# fpga-bank1-outside.net
KiCad netlist of a schematic drawn in Altium Designer
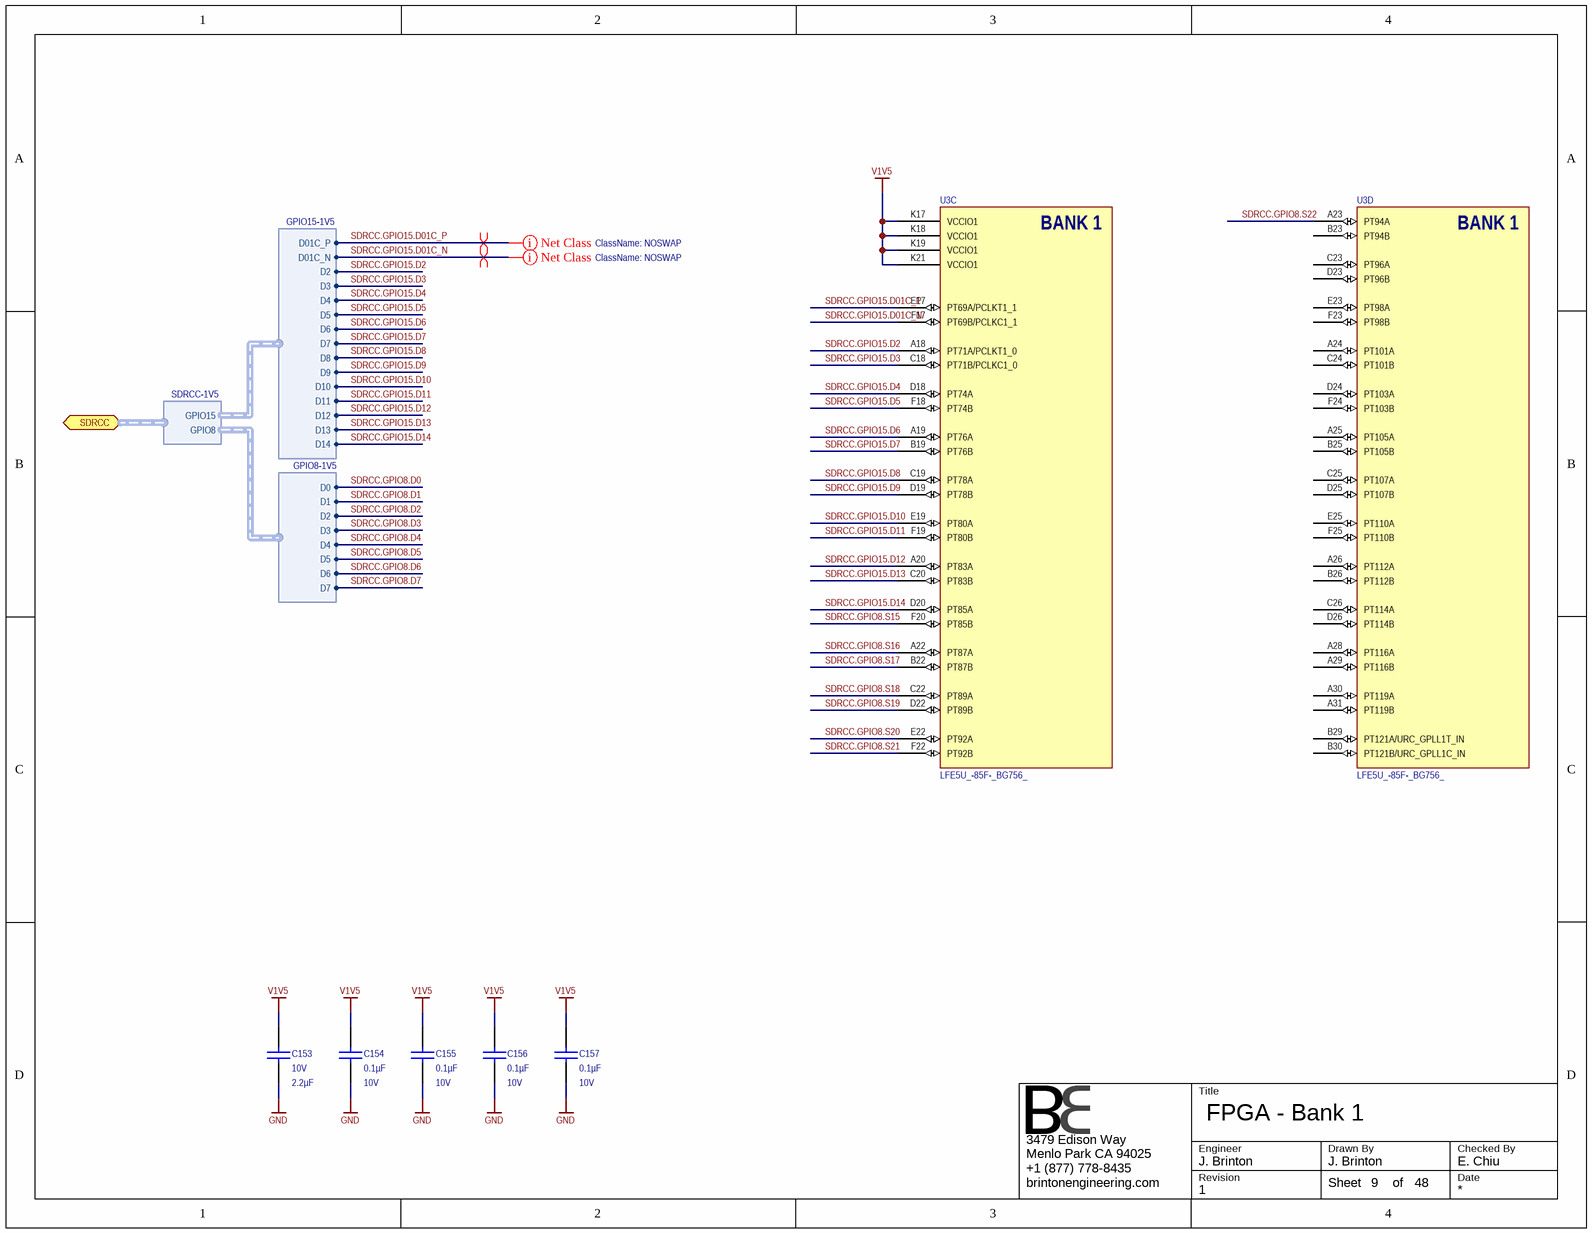
[diagram p0: fpga-bank1-outside.SchDoc]

(export (version "E")
  (design (tool "Eeschema 10.0.6"))
  (components
    (comp (ref "C153")
      (value "GRM188R71A225KE15D")
      (footprint "CAPC1608X90N")
      (description "CAP CER 2.2UF 10V 10% X7R 0603")
      (fields
        (field (name "MANUFACTURER") "Murata Electronics North America")
        (field (name "TOLERANCE") "±10%")
        (field (name "VOLTAGE - RATED") "10V")
        (field (name "CAPACITANCE") "2.2µF")
      )
      (libsource (lib "murata") (part "GRM188R71A225KE15D"))
    )
    (comp (ref "C154")
      (value "GRM155R71A104KA01J")
      (footprint "CAPC1005X56N")
      (description "CAP CER 0.1UF 10V 10% X7R 0402")
      (fields
        (field (name "MANUFACTURER") "Murata Electronics North America")
        (field (name "TOLERANCE") "±10%")
        (field (name "CAPACITANCE") "0.1µF")
        (field (name "VOLTAGE - RATED") "10V")
      )
      (libsource (lib "murata") (part "GRM155R71A104KA01J"))
    )
    (comp (ref "C155")
      (value "GRM155R71A104KA01J")
      (footprint "CAPC1005X56N")
      (description "CAP CER 0.1UF 10V 10% X7R 0402")
      (fields
        (field (name "MANUFACTURER") "Murata Electronics North America")
        (field (name "TOLERANCE") "±10%")
        (field (name "CAPACITANCE") "0.1µF")
        (field (name "VOLTAGE - RATED") "10V")
      )
      (libsource (lib "murata") (part "GRM155R71A104KA01J"))
    )
    (comp (ref "C156")
      (value "GRM155R71A104KA01J")
      (footprint "CAPC1005X56N")
      (description "CAP CER 0.1UF 10V 10% X7R 0402")
      (fields
        (field (name "MANUFACTURER") "Murata Electronics North America")
        (field (name "TOLERANCE") "±10%")
        (field (name "CAPACITANCE") "0.1µF")
        (field (name "VOLTAGE - RATED") "10V")
      )
      (libsource (lib "murata") (part "GRM155R71A104KA01J"))
    )
    (comp (ref "C157")
      (value "GRM155R71A104KA01J")
      (footprint "CAPC1005X56N")
      (description "CAP CER 0.1UF 10V 10% X7R 0402")
      (fields
        (field (name "MANUFACTURER") "Murata Electronics North America")
        (field (name "TOLERANCE") "±10%")
        (field (name "CAPACITANCE") "0.1µF")
        (field (name "VOLTAGE - RATED") "10V")
      )
      (libsource (lib "murata") (part "GRM155R71A104KA01J"))
    )
    (comp (ref "U3")
      (value "LFE5U_-85F-_BG756_")
      (footprint "lattice:caBGA756")
      (description "ECP5 FPGA, 85k LUT, 756-caBGA")
      (fields (field (name "MANUFACTURER") "Lattice Semiconductor"))
      (libsource (lib "lattice") (part "LFE5U_-85F-_BG756_"))
    )
  )
  (nets
    (net (code "11") (name "/SDRCC.GPIO8.S15") (class "Default")
      (node (ref "U3") (pin "F20") (pinfunction "PT85B_F20") (pintype "bidirectional"))
    )
    (net (code "12") (name "/SDRCC.GPIO8.S16") (class "Default")
      (node (ref "U3") (pin "A22") (pinfunction "PT87A_A22") (pintype "bidirectional"))
    )
    (net (code "13") (name "/SDRCC.GPIO8.S17") (class "Default")
      (node (ref "U3") (pin "B22") (pinfunction "PT87B_B22") (pintype "bidirectional"))
    )
    (net (code "14") (name "/SDRCC.GPIO8.S18") (class "Default")
      (node (ref "U3") (pin "C22") (pinfunction "PT89A_C22") (pintype "bidirectional"))
    )
    (net (code "15") (name "/SDRCC.GPIO8.S19") (class "Default")
      (node (ref "U3") (pin "D22") (pinfunction "PT89B_D22") (pintype "bidirectional"))
    )
    (net (code "16") (name "/SDRCC.GPIO8.S20") (class "Default")
      (node (ref "U3") (pin "E22") (pinfunction "PT92A_E22") (pintype "bidirectional"))
    )
    (net (code "17") (name "/SDRCC.GPIO8.S21") (class "Default")
      (node (ref "U3") (pin "F22") (pinfunction "PT92B_F22") (pintype "bidirectional"))
    )
    (net (code "18") (name "/SDRCC.GPIO8.S22") (class "Default")
      (node (ref "U3") (pin "A23") (pinfunction "PT94A_A23") (pintype "bidirectional"))
    )
    (net (code "19") (name "/SDRCC.GPIO15.D01C_N") (class "Default")
      (node (ref "U3") (pin "F17") (pinfunction "PT69B/PCLKC1_1_F17") (pintype "bidirectional"))
    )
    (net (code "20") (name "/SDRCC.GPIO15.D01C_P") (class "Default")
      (node (ref "U3") (pin "E17") (pinfunction "PT69A/PCLKT1_1_E17") (pintype "bidirectional"))
    )
    (net (code "21") (name "/SDRCC.GPIO15.D2") (class "Default")
      (node (ref "U3") (pin "A18") (pinfunction "PT71A/PCLKT1_0_A18") (pintype "bidirectional"))
    )
    (net (code "22") (name "/SDRCC.GPIO15.D3") (class "Default")
      (node (ref "U3") (pin "C18") (pinfunction "PT71B/PCLKC1_0_C18") (pintype "bidirectional"))
    )
    (net (code "23") (name "/SDRCC.GPIO15.D4") (class "Default")
      (node (ref "U3") (pin "D18") (pinfunction "PT74A_D18") (pintype "bidirectional"))
    )
    (net (code "24") (name "/SDRCC.GPIO15.D5") (class "Default")
      (node (ref "U3") (pin "F18") (pinfunction "PT74B_F18") (pintype "bidirectional"))
    )
    (net (code "25") (name "/SDRCC.GPIO15.D6") (class "Default")
      (node (ref "U3") (pin "A19") (pinfunction "PT76A_A19") (pintype "bidirectional"))
    )
    (net (code "26") (name "/SDRCC.GPIO15.D7") (class "Default")
      (node (ref "U3") (pin "B19") (pinfunction "PT76B_B19") (pintype "bidirectional"))
    )
    (net (code "27") (name "/SDRCC.GPIO15.D8") (class "Default")
      (node (ref "U3") (pin "C19") (pinfunction "PT78A_C19") (pintype "bidirectional"))
    )
    (net (code "28") (name "/SDRCC.GPIO15.D9") (class "Default")
      (node (ref "U3") (pin "D19") (pinfunction "PT78B_D19") (pintype "bidirectional"))
    )
    (net (code "29") (name "/SDRCC.GPIO15.D10") (class "Default")
      (node (ref "U3") (pin "E19") (pinfunction "PT80A_E19") (pintype "bidirectional"))
    )
    (net (code "30") (name "/SDRCC.GPIO15.D11") (class "Default")
      (node (ref "U3") (pin "F19") (pinfunction "PT80B_F19") (pintype "bidirectional"))
    )
    (net (code "31") (name "/SDRCC.GPIO15.D12") (class "Default")
      (node (ref "U3") (pin "A20") (pinfunction "PT83A_A20") (pintype "bidirectional"))
    )
    (net (code "32") (name "/SDRCC.GPIO15.D13") (class "Default")
      (node (ref "U3") (pin "C20") (pinfunction "PT83B_C20") (pintype "bidirectional"))
    )
    (net (code "33") (name "/SDRCC.GPIO15.D14") (class "Default")
      (node (ref "U3") (pin "D20") (pinfunction "PT85A_D20") (pintype "bidirectional"))
    )
    (net (code "36") (name "GND") (class "Default")
      (node (ref "C153") (pin "1") (pinfunction "1_1") (pintype "passive"))
      (node (ref "C154") (pin "1") (pinfunction "1_1") (pintype "passive"))
      (node (ref "C155") (pin "1") (pinfunction "1_1") (pintype "passive"))
      (node (ref "C156") (pin "1") (pinfunction "1_1") (pintype "passive"))
      (node (ref "C157") (pin "1") (pinfunction "1_1") (pintype "passive"))
    )
    (net (code "37") (name "V1V5") (class "Default")
      (node (ref "C153") (pin "2") (pinfunction "2_2") (pintype "passive"))
      (node (ref "C154") (pin "2") (pinfunction "2_2") (pintype "passive"))
      (node (ref "C155") (pin "2") (pinfunction "2_2") (pintype "passive"))
      (node (ref "C156") (pin "2") (pinfunction "2_2") (pintype "passive"))
      (node (ref "C157") (pin "2") (pinfunction "2_2") (pintype "passive"))
      (node (ref "U3") (pin "K17") (pinfunction "VCCIO1_K17") (pintype "power_in"))
      (node (ref "U3") (pin "K18") (pinfunction "VCCIO1_K18") (pintype "power_in"))
      (node (ref "U3") (pin "K19") (pinfunction "VCCIO1_K19") (pintype "power_in"))
      (node (ref "U3") (pin "K21") (pinfunction "VCCIO1_K21") (pintype "power_in"))
    )
    (net (code "38") (name "unconnected-(U3D-PT94B-PadB23)") (class "Default")
      (node (ref "U3") (pin "B23") (pinfunction "PT94B_B23") (pintype "bidirectional"))
    )
    (net (code "39") (name "unconnected-(U3D-PT96A-PadC23)") (class "Default")
      (node (ref "U3") (pin "C23") (pinfunction "PT96A_C23") (pintype "bidirectional"))
    )
    (net (code "40") (name "unconnected-(U3D-PT96B-PadD23)") (class "Default")
      (node (ref "U3") (pin "D23") (pinfunction "PT96B_D23") (pintype "bidirectional"))
    )
    (net (code "41") (name "unconnected-(U3D-PT98A-PadE23)") (class "Default")
      (node (ref "U3") (pin "E23") (pinfunction "PT98A_E23") (pintype "bidirectional"))
    )
    (net (code "42") (name "unconnected-(U3D-PT98B-PadF23)") (class "Default")
      (node (ref "U3") (pin "F23") (pinfunction "PT98B_F23") (pintype "bidirectional"))
    )
    (net (code "43") (name "unconnected-(U3D-PT101A-PadA24)") (class "Default")
      (node (ref "U3") (pin "A24") (pinfunction "PT101A_A24") (pintype "bidirectional"))
    )
    (net (code "44") (name "unconnected-(U3D-PT101B-PadC24)") (class "Default")
      (node (ref "U3") (pin "C24") (pinfunction "PT101B_C24") (pintype "bidirectional"))
    )
    (net (code "45") (name "unconnected-(U3D-PT103A-PadD24)") (class "Default")
      (node (ref "U3") (pin "D24") (pinfunction "PT103A_D24") (pintype "bidirectional"))
    )
    (net (code "46") (name "unconnected-(U3D-PT103B-PadF24)") (class "Default")
      (node (ref "U3") (pin "F24") (pinfunction "PT103B_F24") (pintype "bidirectional"))
    )
    (net (code "47") (name "unconnected-(U3D-PT105A-PadA25)") (class "Default")
      (node (ref "U3") (pin "A25") (pinfunction "PT105A_A25") (pintype "bidirectional"))
    )
    (net (code "48") (name "unconnected-(U3D-PT105B-PadB25)") (class "Default")
      (node (ref "U3") (pin "B25") (pinfunction "PT105B_B25") (pintype "bidirectional"))
    )
    (net (code "49") (name "unconnected-(U3D-PT107A-PadC25)") (class "Default")
      (node (ref "U3") (pin "C25") (pinfunction "PT107A_C25") (pintype "bidirectional"))
    )
    (net (code "50") (name "unconnected-(U3D-PT107B-PadD25)") (class "Default")
      (node (ref "U3") (pin "D25") (pinfunction "PT107B_D25") (pintype "bidirectional"))
    )
    (net (code "51") (name "unconnected-(U3D-PT110A-PadE25)") (class "Default")
      (node (ref "U3") (pin "E25") (pinfunction "PT110A_E25") (pintype "bidirectional"))
    )
    (net (code "52") (name "unconnected-(U3D-PT110B-PadF25)") (class "Default")
      (node (ref "U3") (pin "F25") (pinfunction "PT110B_F25") (pintype "bidirectional"))
    )
    (net (code "53") (name "unconnected-(U3D-PT112A-PadA26)") (class "Default")
      (node (ref "U3") (pin "A26") (pinfunction "PT112A_A26") (pintype "bidirectional"))
    )
    (net (code "54") (name "unconnected-(U3D-PT112B-PadB26)") (class "Default")
      (node (ref "U3") (pin "B26") (pinfunction "PT112B_B26") (pintype "bidirectional"))
    )
    (net (code "55") (name "unconnected-(U3D-PT114A-PadC26)") (class "Default")
      (node (ref "U3") (pin "C26") (pinfunction "PT114A_C26") (pintype "bidirectional"))
    )
    (net (code "56") (name "unconnected-(U3D-PT114B-PadD26)") (class "Default")
      (node (ref "U3") (pin "D26") (pinfunction "PT114B_D26") (pintype "bidirectional"))
    )
    (net (code "57") (name "unconnected-(U3D-PT116A-PadA28)") (class "Default")
      (node (ref "U3") (pin "A28") (pinfunction "PT116A_A28") (pintype "bidirectional"))
    )
    (net (code "58") (name "unconnected-(U3D-PT116B-PadA29)") (class "Default")
      (node (ref "U3") (pin "A29") (pinfunction "PT116B_A29") (pintype "bidirectional"))
    )
    (net (code "59") (name "unconnected-(U3D-PT119A-PadA30)") (class "Default")
      (node (ref "U3") (pin "A30") (pinfunction "PT119A_A30") (pintype "bidirectional"))
    )
    (net (code "60") (name "unconnected-(U3D-PT119B-PadA31)") (class "Default")
      (node (ref "U3") (pin "A31") (pinfunction "PT119B_A31") (pintype "bidirectional"))
    )
    (net (code "61") (name "unconnected-(U3D-PT121A{slash}URC_GPLL1T_IN-PadB29)") (class "Default")
      (node (ref "U3") (pin "B29") (pinfunction "PT121A/URC_GPLL1T_IN_B29") (pintype "bidirectional"))
    )
    (net (code "62") (name "unconnected-(U3D-PT121B{slash}URC_GPLL1C_IN-PadB30)") (class "Default")
      (node (ref "U3") (pin "B30") (pinfunction "PT121B/URC_GPLL1C_IN_B30") (pintype "bidirectional"))
    )
  )
)
